# Inverter_v1p1.net
KiCad netlist of a schematic drawn in EAGLE
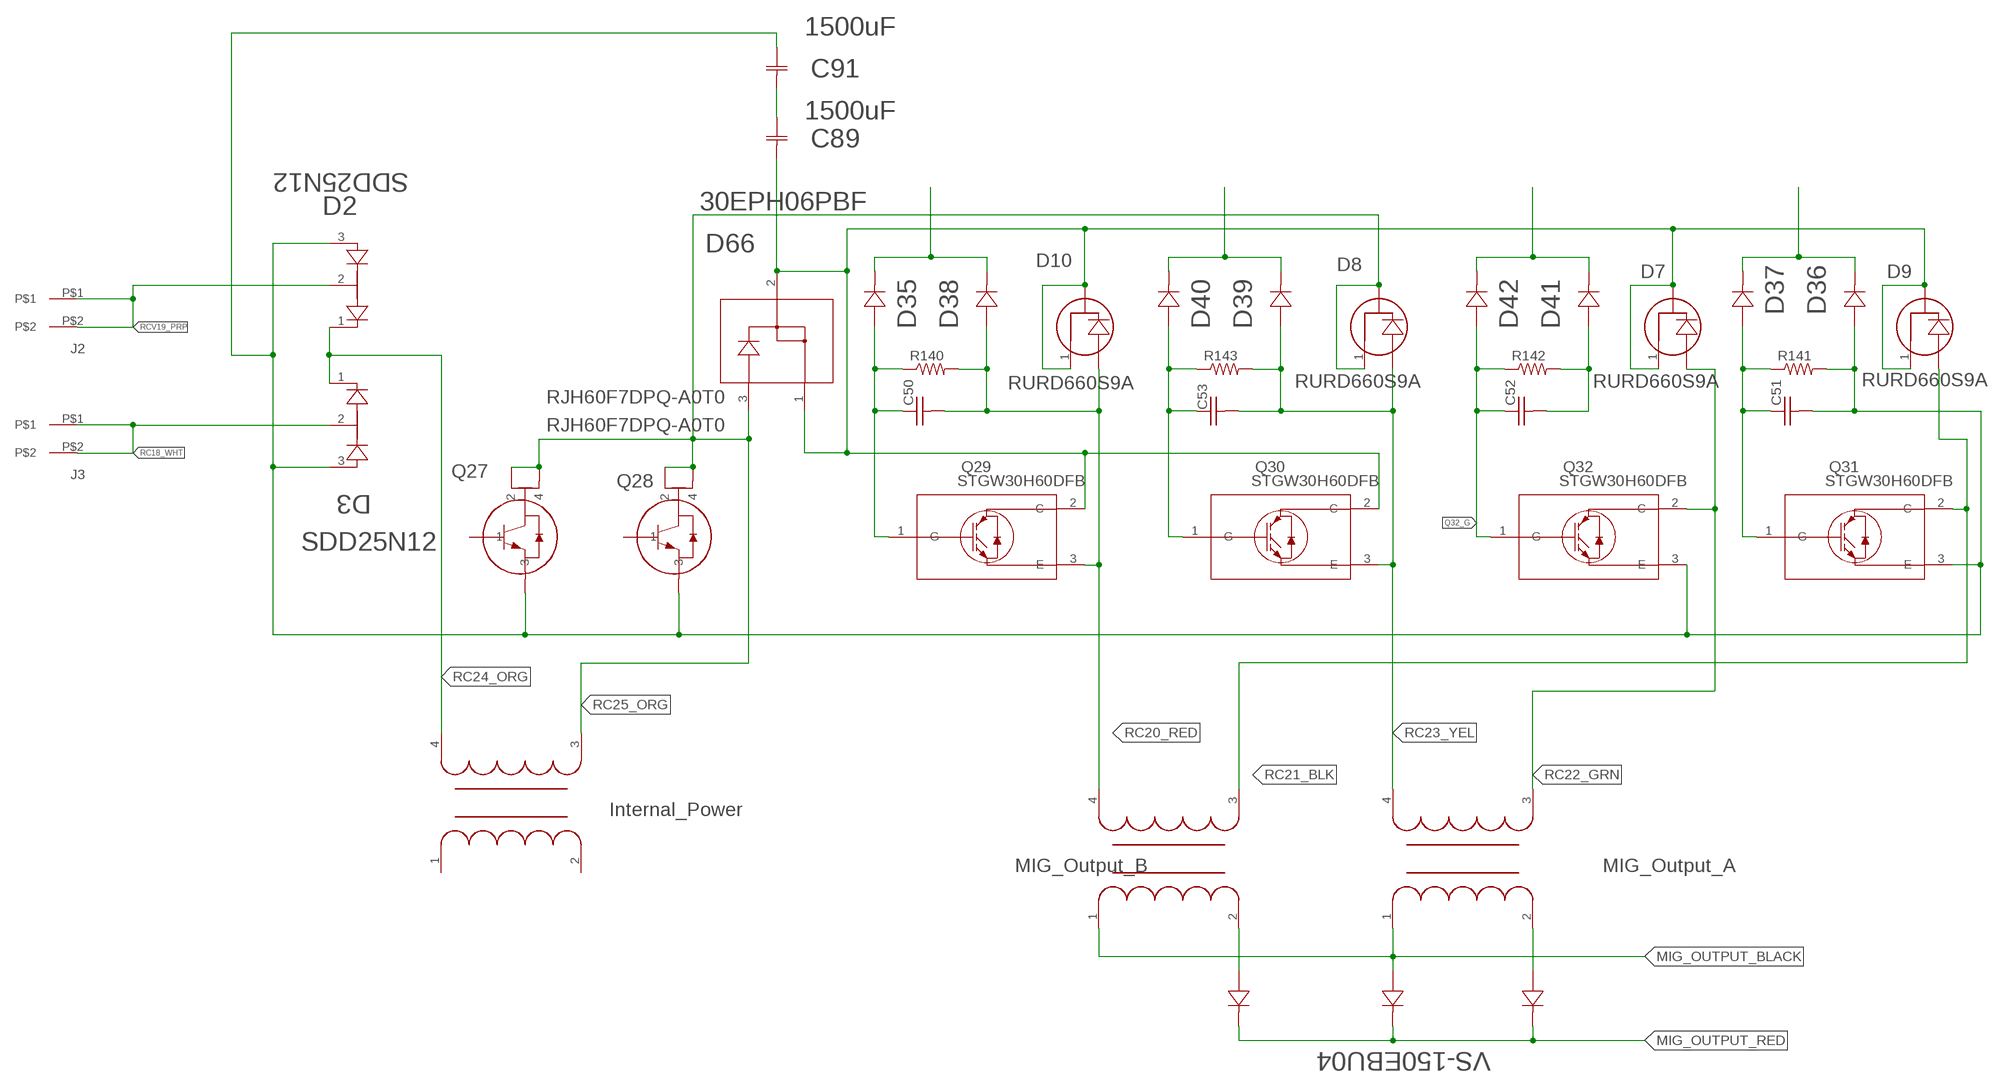
[diagram p0: schematic, sheet 1]

(export (version "E")
  (design (tool "Eeschema 10.0.6"))
  (components
    (comp (ref "C50")
      (value "C_0805")
      (footprint "eagle-import:0805")
      (libsource (lib "eagle-import") (part "C_0805"))
    )
    (comp (ref "C51")
      (value "C_0805")
      (footprint "eagle-import:0805")
      (libsource (lib "eagle-import") (part "C_0805"))
    )
    (comp (ref "C52")
      (value "C_0805")
      (footprint "eagle-import:0805")
      (libsource (lib "eagle-import") (part "C_0805"))
    )
    (comp (ref "C53")
      (value "C_0805")
      (footprint "eagle-import:0805")
      (libsource (lib "eagle-import") (part "C_0805"))
    )
    (comp (ref "C89")
      (value "1500uF")
      (footprint "eagle-import:CAP_SLP152M250H9P3_CND")
      (fields
        (field (name "MANUFACTURER_PART_NUMBER") "SLP152M250H9P3")
        (field (name "COPYRIGHT") "Copyright (C) 2018 Accelerated Designs. All rights reserved")
      )
      (libsource (lib "eagle-import") (part "C_1500UF"))
    )
    (comp (ref "C91")
      (value "1500uF")
      (footprint "eagle-import:CAP_SLP152M250H9P3_CND")
      (fields
        (field (name "MANUFACTURER_PART_NUMBER") "SLP152M250H9P3")
        (field (name "COPYRIGHT") "Copyright (C) 2018 Accelerated Designs. All rights reserved")
      )
      (libsource (lib "eagle-import") (part "C_1500UF"))
    )
    (comp (ref "D2")
      (value "SDD25N12")
      (footprint "eagle-import:TO-247AD")
      (libsource (lib "eagle-import") (part "SDD25N12"))
    )
    (comp (ref "D3")
      (value "SDD25N12")
      (footprint "eagle-import:TO-247AD")
      (libsource (lib "eagle-import") (part "SDD25N12"))
    )
    (comp (ref "D7")
      (value "RURD660S9A")
      (footprint "eagle-import:TO-252")
      (libsource (lib "eagle-import") (part "RURD660S9A"))
    )
    (comp (ref "D8")
      (value "RURD660S9A")
      (footprint "eagle-import:TO-252")
      (libsource (lib "eagle-import") (part "RURD660S9A"))
    )
    (comp (ref "D9")
      (value "RURD660S9A")
      (footprint "eagle-import:TO-252")
      (libsource (lib "eagle-import") (part "RURD660S9A"))
    )
    (comp (ref "D10")
      (value "RURD660S9A")
      (footprint "eagle-import:TO-252")
      (libsource (lib "eagle-import") (part "RURD660S9A"))
    )
    (comp (ref "D35")
      (value "SMAZ18-13-FSMA_DIO-M")
      (footprint "eagle-import:SMA_DIO-M")
      (fields (field (name "MANUFACTURER_PART_NUMBER") "SMAZ18-13-F"))
      (libsource (lib "eagle-import") (part "SMAZ18-13-FSMA_DIO-M"))
    )
    (comp (ref "D36")
      (value "SMAZ18-13-FSMA_DIO-M")
      (footprint "eagle-import:SMA_DIO-M")
      (fields (field (name "MANUFACTURER_PART_NUMBER") "SMAZ18-13-F"))
      (libsource (lib "eagle-import") (part "SMAZ18-13-FSMA_DIO-M"))
    )
    (comp (ref "D37")
      (value "SMAZ18-13-FSMA_DIO-M")
      (footprint "eagle-import:SMA_DIO-M")
      (fields (field (name "MANUFACTURER_PART_NUMBER") "SMAZ18-13-F"))
      (libsource (lib "eagle-import") (part "SMAZ18-13-FSMA_DIO-M"))
    )
    (comp (ref "D38")
      (value "ZJF_638")
      (footprint "eagle-import:SMA_DIO-M")
      (fields (field (name "MANUFACTURER_PART_NUMBER") "SMAZ18-13-F"))
      (libsource (lib "eagle-import") (part "SMAZ18-13-FSMA_DIO-M"))
    )
    (comp (ref "D39")
      (value "SMAZ18-13-FSMA_DIO-M")
      (footprint "eagle-import:SMA_DIO-M")
      (fields (field (name "MANUFACTURER_PART_NUMBER") "SMAZ18-13-F"))
      (libsource (lib "eagle-import") (part "SMAZ18-13-FSMA_DIO-M"))
    )
    (comp (ref "D40")
      (value "SMAZ18-13-FSMA_DIO-M")
      (footprint "eagle-import:SMA_DIO-M")
      (fields (field (name "MANUFACTURER_PART_NUMBER") "SMAZ18-13-F"))
      (libsource (lib "eagle-import") (part "SMAZ18-13-FSMA_DIO-M"))
    )
    (comp (ref "D41")
      (value "SMAZ18-13-FSMA_DIO-M")
      (footprint "eagle-import:SMA_DIO-M")
      (fields (field (name "MANUFACTURER_PART_NUMBER") "SMAZ18-13-F"))
      (libsource (lib "eagle-import") (part "SMAZ18-13-FSMA_DIO-M"))
    )
    (comp (ref "D42")
      (value "SMAZ18-13-FSMA_DIO-M")
      (footprint "eagle-import:SMA_DIO-M")
      (fields (field (name "MANUFACTURER_PART_NUMBER") "SMAZ18-13-F"))
      (libsource (lib "eagle-import") (part "SMAZ18-13-FSMA_DIO-M"))
    )
    (comp (ref "D66")
      (value "30EPH06PBF")
      (footprint "eagle-import:TO-247AC_MOD_VIS")
      (libsource (lib "eagle-import") (part "30EPH06PBF"))
    )
    (comp (ref "J2")
      (value "2-pos")
      (footprint "eagle-import:2_3.81MM_PITCH")
      (fields (field (name "PARTNO") "691322310002"))
      (libsource (lib "eagle-import") (part "3.81MM_1_X_2_RT_ANGLE_PLUG_HEADER"))
    )
    (comp (ref "J3")
      (value "2-pos")
      (footprint "eagle-import:2_3.81MM_PITCH")
      (fields (field (name "PARTNO") "691322310002"))
      (libsource (lib "eagle-import") (part "3.81MM_1_X_2_RT_ANGLE_PLUG_HEADER"))
    )
    (comp (ref "Q27")
      (value "RJH60F7DPQ-A0T0")
      (footprint "eagle-import:TO-247A_REN")
      (fields (field (name "MANUFACTURER_PART_NUMBER") "RJH60F7DPQ-A0#T0"))
      (libsource (lib "eagle-import") (part "RJH60F7DPQ-A0T0"))
    )
    (comp (ref "Q28")
      (value "RJH60F7DPQ-A0T0")
      (footprint "eagle-import:TO-247A_REN")
      (fields (field (name "MANUFACTURER_PART_NUMBER") "RJH60F7DPQ-A0#T0"))
      (libsource (lib "eagle-import") (part "RJH60F7DPQ-A0T0"))
    )
    (comp (ref "Q29")
      (value "STGW30H60DFB")
      (footprint "eagle-import:TO-247_STM")
      (fields (field (name "COPYRIGHT") "Copyright (C) 2018 Accelerated Designs. All rights reserved"))
      (libsource (lib "eagle-import") (part "STGW30H60DFB"))
    )
    (comp (ref "Q30")
      (value "STGW30H60DFB")
      (footprint "eagle-import:TO-247_STM")
      (fields (field (name "COPYRIGHT") "Copyright (C) 2018 Accelerated Designs. All rights reserved"))
      (libsource (lib "eagle-import") (part "STGW30H60DFB"))
    )
    (comp (ref "Q31")
      (value "STGW30H60DFB")
      (footprint "eagle-import:TO-247_STM")
      (fields (field (name "COPYRIGHT") "Copyright (C) 2018 Accelerated Designs. All rights reserved"))
      (libsource (lib "eagle-import") (part "STGW30H60DFB"))
    )
    (comp (ref "Q32")
      (value "STGW30H60DFB")
      (footprint "eagle-import:TO-247_STM")
      (fields (field (name "COPYRIGHT") "Copyright (C) 2018 Accelerated Designs. All rights reserved"))
      (libsource (lib "eagle-import") (part "STGW30H60DFB"))
    )
    (comp (ref "R140")
      (value "R_0805")
      (footprint "eagle-import:0805")
      (libsource (lib "eagle-import") (part "R_0805"))
    )
    (comp (ref "R141")
      (value "R_0805")
      (footprint "eagle-import:0805")
      (libsource (lib "eagle-import") (part "R_0805"))
    )
    (comp (ref "R142")
      (value "R_0805")
      (footprint "eagle-import:0805")
      (libsource (lib "eagle-import") (part "R_0805"))
    )
    (comp (ref "R143")
      (value "R_0805")
      (footprint "eagle-import:0805")
      (libsource (lib "eagle-import") (part "R_0805"))
    )
    (comp (ref "U$1")
      (value "GENERIC_TRANSFORMER")
      (footprint "eagle-import:GENERIC_TRANSFORMER")
      (libsource (lib "eagle-import") (part "GENERIC_TRANSFORMER"))
    )
    (comp (ref "U$2")
      (value "GENERIC_TRANSFORMER")
      (footprint "eagle-import:GENERIC_TRANSFORMER")
      (libsource (lib "eagle-import") (part "GENERIC_TRANSFORMER"))
    )
    (comp (ref "U$3")
      (value "GENERIC_TRANSFORMER")
      (footprint "eagle-import:GENERIC_TRANSFORMER")
      (libsource (lib "eagle-import") (part "GENERIC_TRANSFORMER"))
    )
    (comp (ref "U$4")
      (value "VS-150EBU04")
      (footprint "eagle-import:POWER_TAB")
      (libsource (lib "eagle-import") (part "VS-150EBU04"))
    )
    (comp (ref "U$5")
      (value "VS-150EBU04")
      (footprint "eagle-import:POWER_TAB")
      (libsource (lib "eagle-import") (part "VS-150EBU04"))
    )
    (comp (ref "U$6")
      (value "VS-150EBU04")
      (footprint "eagle-import:POWER_TAB")
      (libsource (lib "eagle-import") (part "VS-150EBU04"))
    )
  )
  (nets
    (net (code "1") (name "MIG_OUTPUT_BLACK") (class "Default")
      (node (ref "U$1") (pin "1") (pinfunction "1_1") (pintype "passive"))
      (node (ref "U$2") (pin "1") (pinfunction "1_1") (pintype "passive"))
      (node (ref "U$5") (pin "2") (pinfunction "2_2") (pintype "passive"))
    )
    (net (code "2") (name "MIG_OUTPUT_RED") (class "Default")
      (node (ref "U$4") (pin "1") (pinfunction "1_1") (pintype "passive"))
      (node (ref "U$5") (pin "1") (pinfunction "1_1") (pintype "passive"))
      (node (ref "U$6") (pin "1") (pinfunction "1_1") (pintype "passive"))
    )
    (net (code "3") (name "Net-(C52-Pad2)") (class "Default")
      (node (ref "C52") (pin "2") (pinfunction "2_2") (pintype "passive"))
      (node (ref "D41") (pin "2") (pinfunction "2_2") (pintype "passive"))
      (node (ref "R142") (pin "2") (pinfunction "2_2") (pintype "passive"))
    )
    (net (code "4") (name "Net-(C89-Pad1)") (class "Default")
      (node (ref "C89") (pin "1") (pinfunction "1_1") (pintype "passive"))
      (node (ref "C91") (pin "2") (pinfunction "2_2") (pintype "passive"))
    )
    (net (code "5") (name "Net-(D10-C1)") (class "Default")
      (node (ref "C89") (pin "2") (pinfunction "2_2") (pintype "passive"))
      (node (ref "D10") (pin "1") (pinfunction "C1_1") (pintype "passive"))
      (node (ref "D10") (pin "3") (pinfunction "C2_3") (pintype "passive"))
      (node (ref "D66") (pin "1") (pinfunction "1_1") (pintype "passive"))
      (node (ref "D66") (pin "2") (pinfunction "2_2") (pintype "passive"))
      (node (ref "D7") (pin "1") (pinfunction "C1_1") (pintype "passive"))
      (node (ref "D7") (pin "3") (pinfunction "C2_3") (pintype "passive"))
      (node (ref "D9") (pin "1") (pinfunction "C1_1") (pintype "passive"))
      (node (ref "D9") (pin "3") (pinfunction "C2_3") (pintype "passive"))
      (node (ref "Q29") (pin "2") (pinfunction "C_2") (pintype "passive"))
      (node (ref "Q30") (pin "2") (pinfunction "C_2") (pintype "passive"))
    )
    (net (code "6") (name "Net-(D35-Pad1)") (class "Default")
      (node (ref "D35") (pin "1") (pinfunction "1_1") (pintype "passive"))
      (node (ref "D38") (pin "1") (pinfunction "1_1") (pintype "passive"))
    )
    (net (code "7") (name "Net-(D36-Pad1)") (class "Default")
      (node (ref "D36") (pin "1") (pinfunction "1_1") (pintype "passive"))
      (node (ref "D37") (pin "1") (pinfunction "1_1") (pintype "passive"))
    )
    (net (code "8") (name "Net-(D39-Pad1)") (class "Default")
      (node (ref "D39") (pin "1") (pinfunction "1_1") (pintype "passive"))
      (node (ref "D40") (pin "1") (pinfunction "1_1") (pintype "passive"))
    )
    (net (code "9") (name "Net-(D41-Pad1)") (class "Default")
      (node (ref "D41") (pin "1") (pinfunction "1_1") (pintype "passive"))
      (node (ref "D42") (pin "1") (pinfunction "1_1") (pintype "passive"))
    )
    (net (code "10") (name "Net-(Q29-G)") (class "Default")
      (node (ref "C50") (pin "1") (pinfunction "1_1") (pintype "passive"))
      (node (ref "D35") (pin "2") (pinfunction "2_2") (pintype "passive"))
      (node (ref "Q29") (pin "1") (pinfunction "G_1") (pintype "passive"))
      (node (ref "R140") (pin "1") (pinfunction "1_1") (pintype "passive"))
    )
    (net (code "11") (name "Net-(Q30-G)") (class "Default")
      (node (ref "C53") (pin "1") (pinfunction "1_1") (pintype "passive"))
      (node (ref "D40") (pin "2") (pinfunction "2_2") (pintype "passive"))
      (node (ref "Q30") (pin "1") (pinfunction "G_1") (pintype "passive"))
      (node (ref "R143") (pin "1") (pinfunction "1_1") (pintype "passive"))
    )
    (net (code "12") (name "Net-(Q31-E)") (class "Default")
      (node (ref "C51") (pin "2") (pinfunction "2_2") (pintype "passive"))
      (node (ref "C91") (pin "1") (pinfunction "1_1") (pintype "passive"))
      (node (ref "D2") (pin "3") (pinfunction "3_3") (pintype "passive"))
      (node (ref "D3") (pin "3") (pinfunction "3_3") (pintype "passive"))
      (node (ref "D36") (pin "2") (pinfunction "2_2") (pintype "passive"))
      (node (ref "Q27") (pin "3") (pinfunction "3_3") (pintype "passive"))
      (node (ref "Q28") (pin "3") (pinfunction "3_3") (pintype "passive"))
      (node (ref "Q31") (pin "3") (pinfunction "E_3") (pintype "passive"))
      (node (ref "Q32") (pin "3") (pinfunction "E_3") (pintype "passive"))
      (node (ref "R141") (pin "2") (pinfunction "2_2") (pintype "passive"))
    )
    (net (code "13") (name "Net-(Q31-G)") (class "Default")
      (node (ref "C51") (pin "1") (pinfunction "1_1") (pintype "passive"))
      (node (ref "D37") (pin "2") (pinfunction "2_2") (pintype "passive"))
      (node (ref "Q31") (pin "1") (pinfunction "G_1") (pintype "passive"))
      (node (ref "R141") (pin "1") (pinfunction "1_1") (pintype "passive"))
    )
    (net (code "14") (name "Net-(U$1-Pad2)") (class "Default")
      (node (ref "U$1") (pin "2") (pinfunction "2_2") (pintype "passive"))
      (node (ref "U$4") (pin "2") (pinfunction "2_2") (pintype "passive"))
    )
    (net (code "15") (name "Net-(U$2-Pad2)") (class "Default")
      (node (ref "U$2") (pin "2") (pinfunction "2_2") (pintype "passive"))
      (node (ref "U$6") (pin "2") (pinfunction "2_2") (pintype "passive"))
    )
    (net (code "16") (name "Q32_G") (class "Default")
      (node (ref "C52") (pin "1") (pinfunction "1_1") (pintype "passive"))
      (node (ref "D42") (pin "2") (pinfunction "2_2") (pintype "passive"))
      (node (ref "Q32") (pin "1") (pinfunction "G_1") (pintype "passive"))
      (node (ref "R142") (pin "1") (pinfunction "1_1") (pintype "passive"))
    )
    (net (code "17") (name "RC18_WHT") (class "Default")
      (node (ref "D3") (pin "2") (pinfunction "2_2") (pintype "passive"))
      (node (ref "J3") (pin "P$1") (pinfunction "P$1_P$1") (pintype "bidirectional"))
      (node (ref "J3") (pin "P$2") (pinfunction "P$2_P$2") (pintype "bidirectional"))
    )
    (net (code "18") (name "RC20_RED") (class "Default")
      (node (ref "C50") (pin "2") (pinfunction "2_2") (pintype "passive"))
      (node (ref "D10") (pin "2") (pinfunction "A_2") (pintype "passive"))
      (node (ref "D38") (pin "2") (pinfunction "2_2") (pintype "passive"))
      (node (ref "Q29") (pin "3") (pinfunction "E_3") (pintype "passive"))
      (node (ref "R140") (pin "2") (pinfunction "2_2") (pintype "passive"))
      (node (ref "U$1") (pin "4") (pinfunction "4_4") (pintype "passive"))
    )
    (net (code "19") (name "RC21_BLK") (class "Default")
      (node (ref "D9") (pin "2") (pinfunction "A_2") (pintype "passive"))
      (node (ref "Q31") (pin "2") (pinfunction "C_2") (pintype "passive"))
      (node (ref "U$1") (pin "3") (pinfunction "3_3") (pintype "passive"))
    )
    (net (code "20") (name "RC22_GRN") (class "Default")
      (node (ref "D7") (pin "2") (pinfunction "A_2") (pintype "passive"))
      (node (ref "Q32") (pin "2") (pinfunction "C_2") (pintype "passive"))
      (node (ref "U$2") (pin "3") (pinfunction "3_3") (pintype "passive"))
    )
    (net (code "21") (name "RC23_YEL") (class "Default")
      (node (ref "C53") (pin "2") (pinfunction "2_2") (pintype "passive"))
      (node (ref "D39") (pin "2") (pinfunction "2_2") (pintype "passive"))
      (node (ref "D8") (pin "2") (pinfunction "A_2") (pintype "passive"))
      (node (ref "Q30") (pin "3") (pinfunction "E_3") (pintype "passive"))
      (node (ref "R143") (pin "2") (pinfunction "2_2") (pintype "passive"))
      (node (ref "U$2") (pin "4") (pinfunction "4_4") (pintype "passive"))
    )
    (net (code "22") (name "RC24_ORG") (class "Default")
      (node (ref "D2") (pin "1") (pinfunction "1_1") (pintype "passive"))
      (node (ref "D3") (pin "1") (pinfunction "1_1") (pintype "passive"))
      (node (ref "U$3") (pin "4") (pinfunction "4_4") (pintype "passive"))
    )
    (net (code "23") (name "RC25_ORG") (class "Default")
      (node (ref "D66") (pin "3") (pinfunction "3_3") (pintype "passive"))
      (node (ref "D8") (pin "1") (pinfunction "C1_1") (pintype "passive"))
      (node (ref "D8") (pin "3") (pinfunction "C2_3") (pintype "passive"))
      (node (ref "Q27") (pin "2") (pinfunction "2_2") (pintype "passive"))
      (node (ref "Q27") (pin "4") (pinfunction "4_4") (pintype "passive"))
      (node (ref "Q28") (pin "2") (pinfunction "2_2") (pintype "passive"))
      (node (ref "Q28") (pin "4") (pinfunction "4_4") (pintype "passive"))
      (node (ref "U$3") (pin "3") (pinfunction "3_3") (pintype "passive"))
    )
    (net (code "24") (name "RCV19_PRP") (class "Default")
      (node (ref "D2") (pin "2") (pinfunction "2_2") (pintype "passive"))
      (node (ref "J2") (pin "P$1") (pinfunction "P$1_P$1") (pintype "bidirectional"))
      (node (ref "J2") (pin "P$2") (pinfunction "P$2_P$2") (pintype "bidirectional"))
    )
    (net (code "25") (name "unconnected-(Q27-Pad1)") (class "Default")
      (node (ref "Q27") (pin "1") (pinfunction "1_1") (pintype "passive"))
    )
    (net (code "26") (name "unconnected-(Q28-Pad1)") (class "Default")
      (node (ref "Q28") (pin "1") (pinfunction "1_1") (pintype "passive"))
    )
    (net (code "27") (name "unconnected-(U$3-Pad1)") (class "Default")
      (node (ref "U$3") (pin "1") (pinfunction "1_1") (pintype "passive"))
    )
    (net (code "28") (name "unconnected-(U$3-Pad2)") (class "Default")
      (node (ref "U$3") (pin "2") (pinfunction "2_2") (pintype "passive"))
    )
  )
)
